# Schematic_v6.net
KiCad netlist of a schematic drawn in EAGLE
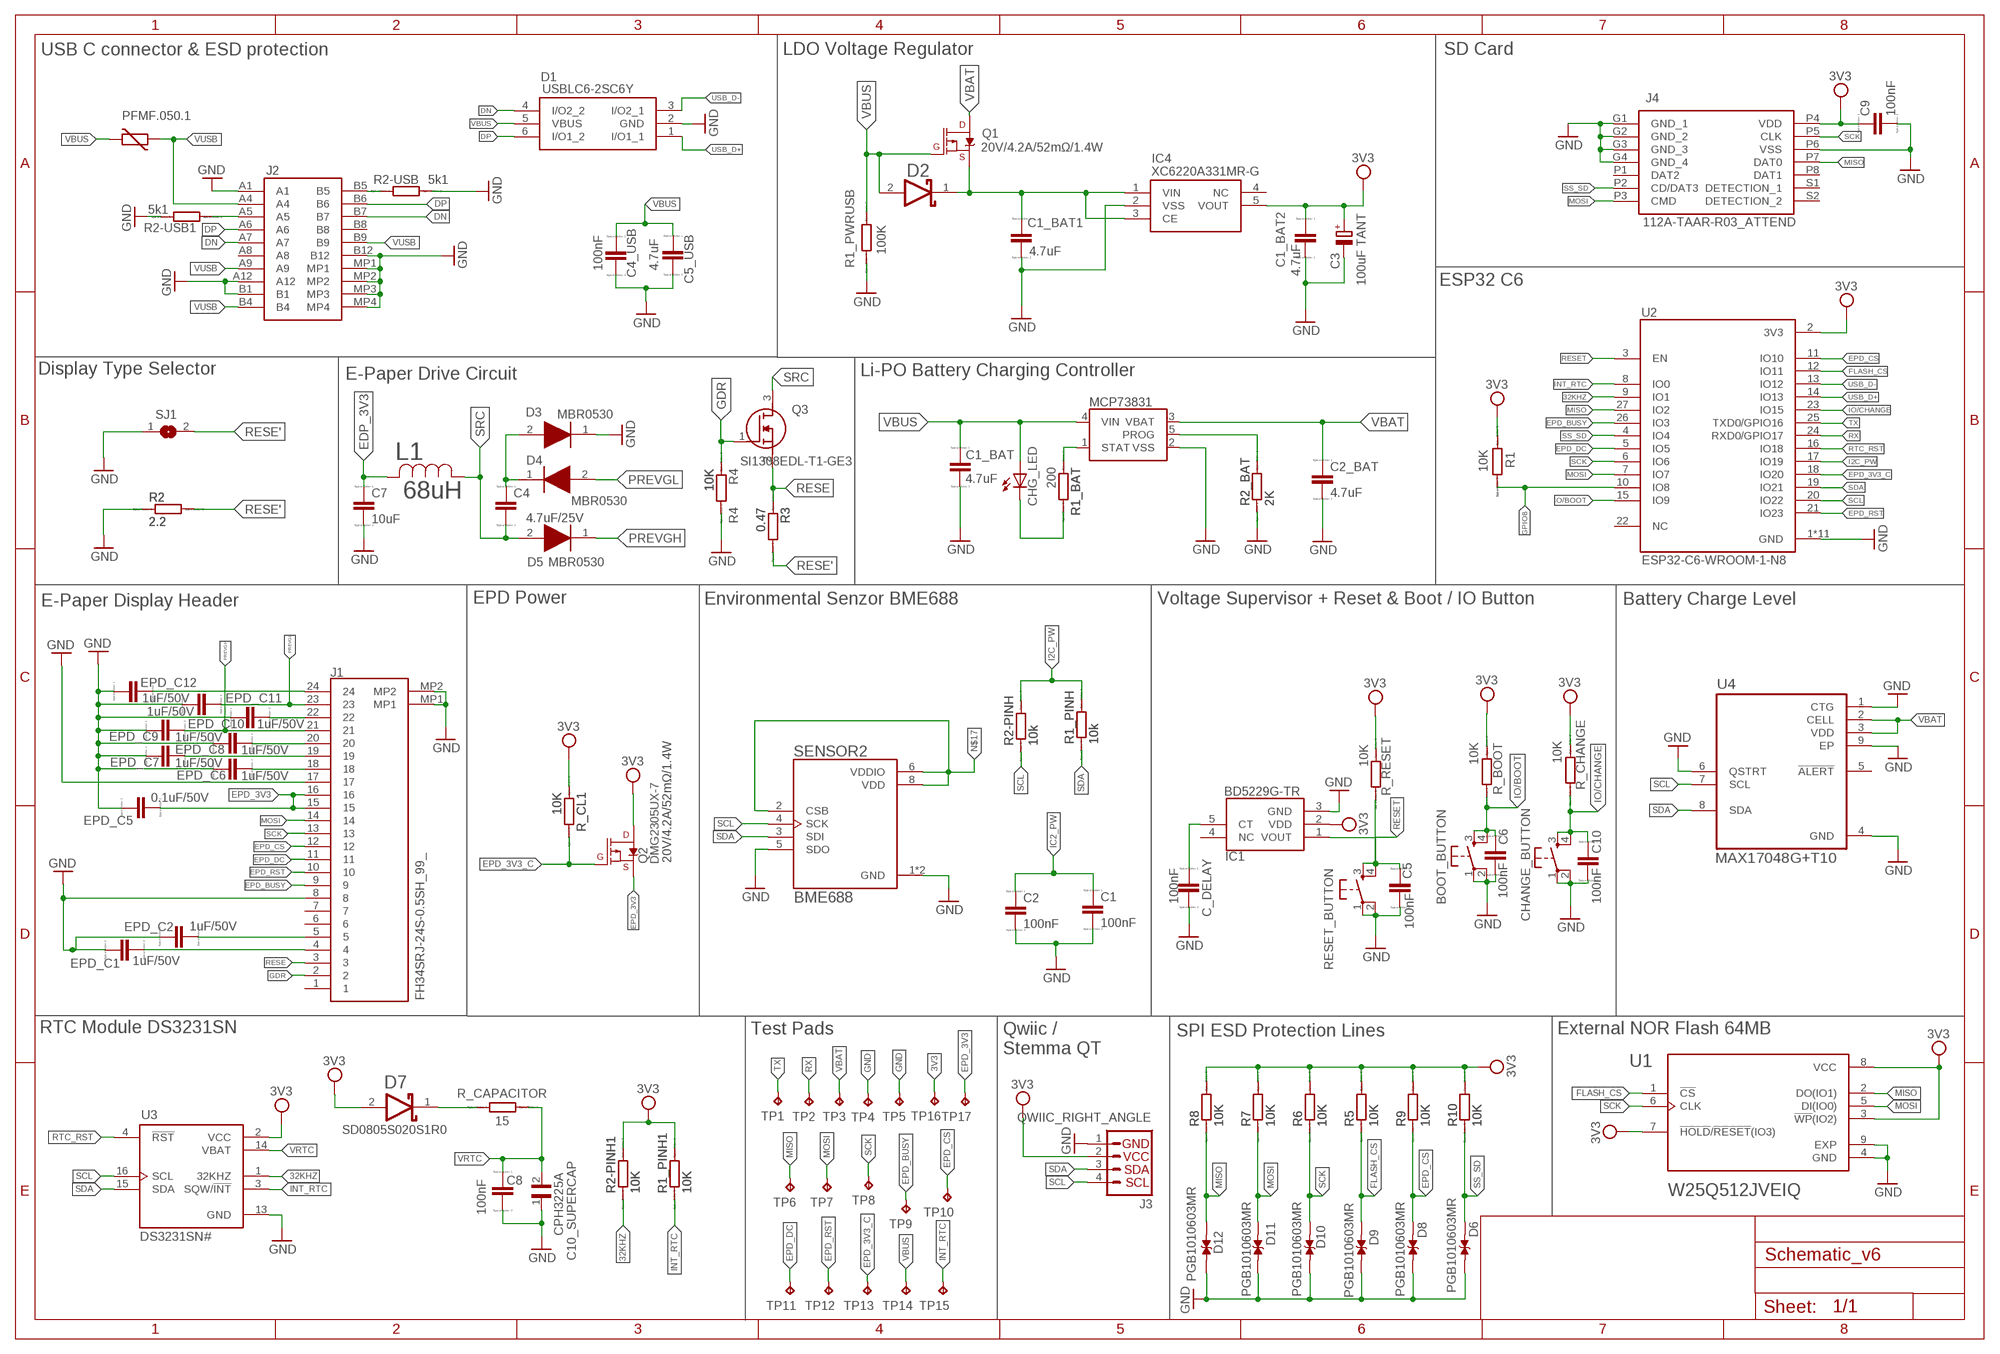
[diagram p0: schematic, sheet 1]

(export (version "E")
  (design (tool "Eeschema 10.0.6"))
  (components
    (comp (ref "BOOT_BUTTON")
      (value "BUTTON_CUSYOMV1")
      (footprint "eagle-import:MYBUTTON")
      (libsource (lib "eagle-import") (part "BUTTON_CUSYOMV1"))
    )
    (comp (ref "C1")
      (value "100nF")
      (footprint "eagle-import:ESP32_WROVER_EAGLE-LTSPICE_C0402")
      (libsource (lib "eagle-import") (part "ESP32_WROVER_EAGLE-LTSPICE_CC0402"))
    )
    (comp (ref "C1_BAT")
      (value "4.7uF")
      (footprint "eagle-import:ESP32_WROVER_EAGLE-LTSPICE_C0402")
      (libsource (lib "eagle-import") (part "ESP32_WROVER_EAGLE-LTSPICE_CC0402"))
    )
    (comp (ref "C1_BAT1")
      (value "4.7uF")
      (footprint "eagle-import:ESP32_WROVER_EAGLE-LTSPICE_C0402")
      (libsource (lib "eagle-import") (part "ESP32_WROVER_EAGLE-LTSPICE_CC0402"))
    )
    (comp (ref "C1_BAT2")
      (value "4.7uF")
      (footprint "eagle-import:ESP32_WROVER_EAGLE-LTSPICE_C0402")
      (libsource (lib "eagle-import") (part "ESP32_WROVER_EAGLE-LTSPICE_CC0402"))
    )
    (comp (ref "C2")
      (value "100nF")
      (footprint "eagle-import:ESP32_WROVER_EAGLE-LTSPICE_C0402")
      (libsource (lib "eagle-import") (part "ESP32_WROVER_EAGLE-LTSPICE_CC0402"))
    )
    (comp (ref "C2_BAT")
      (value "4.7uF")
      (footprint "eagle-import:ESP32_WROVER_EAGLE-LTSPICE_C0402")
      (libsource (lib "eagle-import") (part "ESP32_WROVER_EAGLE-LTSPICE_CC0402"))
    )
    (comp (ref "C3")
      (value "100uF TANT")
      (footprint "eagle-import:RCL_CT3528")
      (libsource (lib "eagle-import") (part "RCL_CPOL-EUCT3528"))
    )
    (comp (ref "C4")
      (value "4.7uF/25V")
      (footprint "eagle-import:ESP32_WROVER_EAGLE-LTSPICE_C0402")
      (libsource (lib "eagle-import") (part "ESP32_WROVER_EAGLE-LTSPICE_CC0402"))
    )
    (comp (ref "C4_USB")
      (value "100nF")
      (footprint "eagle-import:ESP32_WROVER_EAGLE-LTSPICE_C0402")
      (libsource (lib "eagle-import") (part "ESP32_WROVER_EAGLE-LTSPICE_CC0402"))
    )
    (comp (ref "C5")
      (value "100nF")
      (footprint "eagle-import:EAGLE-LTSPICE_C0402")
      (libsource (lib "eagle-import") (part "EAGLE-LTSPICE_CC0402"))
    )
    (comp (ref "C5_USB")
      (value "4.7uF")
      (footprint "eagle-import:ESP32_WROVER_EAGLE-LTSPICE_C0402")
      (libsource (lib "eagle-import") (part "ESP32_WROVER_EAGLE-LTSPICE_CC0402"))
    )
    (comp (ref "C6")
      (value "100nF")
      (footprint "eagle-import:EAGLE-LTSPICE_C0402")
      (libsource (lib "eagle-import") (part "EAGLE-LTSPICE_CC0402"))
    )
    (comp (ref "C7")
      (value "10uF")
      (footprint "eagle-import:ESP32_WROVER_EAGLE-LTSPICE_C0402")
      (libsource (lib "eagle-import") (part "ESP32_WROVER_EAGLE-LTSPICE_CC0402"))
    )
    (comp (ref "C8")
      (value "100nF")
      (footprint "eagle-import:ESP32_WROVER_EAGLE-LTSPICE_C0402")
      (libsource (lib "eagle-import") (part "ESP32_WROVER_EAGLE-LTSPICE_CC0402"))
    )
    (comp (ref "C9")
      (value "100nF")
      (footprint "eagle-import:ESP32_WROVER_EAGLE-LTSPICE_C0402")
      (libsource (lib "eagle-import") (part "ESP32_WROVER_EAGLE-LTSPICE_CC0402"))
    )
    (comp (ref "C10")
      (value "100nF")
      (footprint "eagle-import:EAGLE-LTSPICE_C0402")
      (libsource (lib "eagle-import") (part "EAGLE-LTSPICE_CC0402"))
    )
    (comp (ref "C10_SUPERCAP")
      (value "CPH3225A")
      (footprint "eagle-import:CAPCP3225X100N")
      (fields (field (name "MF") "Seiko Instruments"))
      (libsource (lib "eagle-import") (part "CPH3225A"))
    )
    (comp (ref "CHANGE_BUTTON")
      (value "BUTTON_CUSYOMV1")
      (footprint "eagle-import:MYBUTTON")
      (libsource (lib "eagle-import") (part "BUTTON_CUSYOMV1"))
    )
    (comp (ref "CHG_LED")
      (value "CHG")
      (footprint "eagle-import:ADAFRUIT_CHIP-LED0603")
      (libsource (lib "eagle-import") (part "ADAFRUIT_LEDCHIP-LED0603"))
    )
    (comp (ref "C_DELAY")
      (value "100nF")
      (footprint "eagle-import:ESP32_WROVER_EAGLE-LTSPICE_C0402")
      (libsource (lib "eagle-import") (part "ESP32_WROVER_EAGLE-LTSPICE_CC0402"))
    )
    (comp (ref "D1")
      (value "USBLC6-2SC6Y")
      (footprint "eagle-import:SOT95P280X145-6N")
      (fields (field (name "MF") "STMicroelectronics"))
      (libsource (lib "eagle-import") (part "USBLC6-2SC6Y"))
    )
    (comp (ref "D2")
      (value "ESP32_WROVER_AVX---SD0805S020S1R0_AVX_SD0805S020S1R0_0_0AVX_SD0805S020S1R0_0_0")
      (footprint "eagle-import:ESP32_WROVER_AVX---SD0805S020S1R0_AVX_SD0805S020S1R0_0")
      (fields
        (field (name "DIGIKEY_PART_NUMBER") "478-7800-1-ND")
        (field (name "MF") "AVX")
        (field (name "MOUSER_PART_NUMBER") "581-SD0805S020S1R0")
      )
      (libsource (lib "eagle-import") (part "ESP32_WROVER_AVX---SD0805S020S1R0_AVX_SD0805S020S1R0_0_0AVX_SD0805S020S1R0_0_0"))
    )
    (comp (ref "D3")
      (value "MBR0530")
      (footprint "eagle-import:SOD3716X135N")
      (fields (field (name "MF") "ON Semiconductor"))
      (libsource (lib "eagle-import") (part "MBR0530"))
    )
    (comp (ref "D4")
      (value "MBR0530")
      (footprint "eagle-import:SOD3716X135N")
      (fields (field (name "MF") "ON Semiconductor"))
      (libsource (lib "eagle-import") (part "MBR0530"))
    )
    (comp (ref "D5")
      (value "MBR0530")
      (footprint "eagle-import:SOD3716X135N")
      (fields (field (name "MF") "ON Semiconductor"))
      (libsource (lib "eagle-import") (part "MBR0530"))
    )
    (comp (ref "D6")
      (value "PGB1010603MR")
      (footprint "eagle-import:DIOC1608X36N")
      (fields (field (name "MF") "Littelfuse Inc."))
      (libsource (lib "eagle-import") (part "PGB1010603MR"))
    )
    (comp (ref "D7")
      (value "ESP32_WROVER_AVX---SD0805S020S1R0_AVX_SD0805S020S1R0_0_0AVX_SD0805S020S1R0_0_0")
      (footprint "eagle-import:ESP32_WROVER_AVX---SD0805S020S1R0_AVX_SD0805S020S1R0_0")
      (fields
        (field (name "DIGIKEY_PART_NUMBER") "478-7800-1-ND")
        (field (name "MF") "AVX")
        (field (name "MOUSER_PART_NUMBER") "581-SD0805S020S1R0")
      )
      (libsource (lib "eagle-import") (part "ESP32_WROVER_AVX---SD0805S020S1R0_AVX_SD0805S020S1R0_0_0AVX_SD0805S020S1R0_0_0"))
    )
    (comp (ref "D8")
      (value "PGB1010603MR")
      (footprint "eagle-import:DIOC1608X36N")
      (fields (field (name "MF") "Littelfuse Inc."))
      (libsource (lib "eagle-import") (part "PGB1010603MR"))
    )
    (comp (ref "D9")
      (value "PGB1010603MR")
      (footprint "eagle-import:DIOC1608X36N")
      (fields (field (name "MF") "Littelfuse Inc."))
      (libsource (lib "eagle-import") (part "PGB1010603MR"))
    )
    (comp (ref "D10")
      (value "PGB1010603MR")
      (footprint "eagle-import:DIOC1608X36N")
      (fields (field (name "MF") "Littelfuse Inc."))
      (libsource (lib "eagle-import") (part "PGB1010603MR"))
    )
    (comp (ref "D11")
      (value "PGB1010603MR")
      (footprint "eagle-import:DIOC1608X36N")
      (fields (field (name "MF") "Littelfuse Inc."))
      (libsource (lib "eagle-import") (part "PGB1010603MR"))
    )
    (comp (ref "D12")
      (value "PGB1010603MR")
      (footprint "eagle-import:DIOC1608X36N")
      (fields (field (name "MF") "Littelfuse Inc."))
      (libsource (lib "eagle-import") (part "PGB1010603MR"))
    )
    (comp (ref "EPD_C1")
      (value "1uF/50V")
      (footprint "eagle-import:EAGLE-LTSPICE_C0402")
      (libsource (lib "eagle-import") (part "EAGLE-LTSPICE_CC0402"))
    )
    (comp (ref "EPD_C2")
      (value "1uF/50V")
      (footprint "eagle-import:EAGLE-LTSPICE_C0402")
      (libsource (lib "eagle-import") (part "EAGLE-LTSPICE_CC0402"))
    )
    (comp (ref "EPD_C5")
      (value "0.1uF/50V")
      (footprint "eagle-import:EAGLE-LTSPICE_C0402")
      (libsource (lib "eagle-import") (part "EAGLE-LTSPICE_CC0402"))
    )
    (comp (ref "EPD_C6")
      (value "1uF/50V")
      (footprint "eagle-import:EAGLE-LTSPICE_C0402")
      (libsource (lib "eagle-import") (part "EAGLE-LTSPICE_CC0402"))
    )
    (comp (ref "EPD_C7")
      (value "1uF/50V")
      (footprint "eagle-import:EAGLE-LTSPICE_C0402")
      (libsource (lib "eagle-import") (part "EAGLE-LTSPICE_CC0402"))
    )
    (comp (ref "EPD_C8")
      (value "1uF/50V")
      (footprint "eagle-import:EAGLE-LTSPICE_C0402")
      (libsource (lib "eagle-import") (part "EAGLE-LTSPICE_CC0402"))
    )
    (comp (ref "EPD_C9")
      (value "1uF/50V")
      (footprint "eagle-import:EAGLE-LTSPICE_C0402")
      (libsource (lib "eagle-import") (part "EAGLE-LTSPICE_CC0402"))
    )
    (comp (ref "EPD_C10")
      (value "1uF/50V")
      (footprint "eagle-import:EAGLE-LTSPICE_C0402")
      (libsource (lib "eagle-import") (part "EAGLE-LTSPICE_CC0402"))
    )
    (comp (ref "EPD_C11")
      (value "1uF/50V")
      (footprint "eagle-import:EAGLE-LTSPICE_C0402")
      (libsource (lib "eagle-import") (part "EAGLE-LTSPICE_CC0402"))
    )
    (comp (ref "EPD_C12")
      (value "1uF/50V")
      (footprint "eagle-import:EAGLE-LTSPICE_C0402")
      (libsource (lib "eagle-import") (part "EAGLE-LTSPICE_CC0402"))
    )
    (comp (ref "IC1")
      (value "BD5229G-TR")
      (footprint "eagle-import:SOT95P280X125-5N")
      (fields (field (name "MOUSER_PART_NUMBER") "755-BD5229G-TR"))
      (libsource (lib "eagle-import") (part "BD5229G-TR"))
    )
    (comp (ref "IC4")
      (value "XC6220A331MR-G")
      (footprint "eagle-import:SOT95P280X120-5N")
      (fields (field (name "MOUSER_PART_NUMBER") "865-XC6220A331MR-G"))
      (libsource (lib "eagle-import") (part "XC6220A331MR-G"))
    )
    (comp (ref "J1")
      (value "FH34SRJ-24S-0.5SH_99_")
      (footprint "eagle-import:FH34SRJ24S05SH99")
      (fields
        (field (name "MANUFACTURER_PART_NUMBER") "FH34SRJ-24S-0.5SH(99)")
        (field (name "MOUSER_PART_NUMBER") "798-FH34SRJ24S05SH99")
      )
      (libsource (lib "eagle-import") (part "FH34SRJ-24S-0.5SH_99_"))
    )
    (comp (ref "J2")
      (value "SAMACSYS_PARTS_USB4110-GF-A")
      (footprint "eagle-import:SAMACSYS_PARTS_USB4110GFA")
      (fields
        (field (name "MANUFACTURER_PART_NUMBER") "USB4110-GF-A")
        (field (name "MOUSER_PART_NUMBER") "640-USB4110-GF-A")
      )
      (libsource (lib "eagle-import") (part "SAMACSYS_PARTS_USB4110-GF-A"))
    )
    (comp (ref "J3")
      (value "QWIIC_RIGHT_ANGLE")
      (footprint "eagle-import:JST04_1MM_RA")
      (libsource (lib "eagle-import") (part "QWIIC_CONNECTORJS-1MM"))
    )
    (comp (ref "J4")
      (value "112A-TAAR-R03_ATTEND")
      (footprint "eagle-import:112ATAARR03ATTEND")
      (fields (field (name "MANUFACTURER_PART_NUMBER") "112A-TAAR-R03 ATTEND"))
      (libsource (lib "eagle-import") (part "112A-TAAR-R03_ATTEND"))
    )
    (comp (ref "L1")
      (value "68uH")
      (footprint "eagle-import:IND_4828-WE-TPC_WRE")
      (fields
        (field (name "MANUFACTURER_PART_NUMBER") "744043680")
        (field (name "COPYRIGHT") "Copyright (C) 2024 Ultra Librarian. All rights reserved.")
      )
      (libsource (lib "eagle-import") (part "744043680IND_4828-WE-TPC_WRE"))
    )
    (comp (ref "MCP73831")
      (value "ESP32_WROVER_SPARKFUN-IC-POWER_MCP73831")
      (footprint "eagle-import:ESP32_WROVER_SPARKFUN-IC-POWER_SOT23-5")
      (libsource (lib "eagle-import") (part "ESP32_WROVER_SPARKFUN-IC-POWER_MCP73831"))
    )
    (comp (ref "PFMF.050.1")
      (value "ESP32C6_VARISTORCN1812")
      (footprint "eagle-import:ESP32C6_VARISTOR_CT_CN1812")
      (libsource (lib "eagle-import") (part "ESP32C6_VARISTORCN1812"))
    )
    (comp (ref "Q1")
      (value "20V/4.2A/52mΩ/1.4W")
      (footprint "eagle-import:ESP32_WROVER_SPARKFUN-DISCRETESEMI_SOT23-3")
      (libsource (lib "eagle-import") (part "ESP32_WROVER_SPARKFUN-DISCRETESEMI_MOSFET_PCH-DMG2305UX-7"))
    )
    (comp (ref "Q2")
      (value "20V/4.2A/52mΩ/1.4W")
      (footprint "eagle-import:ESP32_WROVER_SPARKFUN-DISCRETESEMI_SOT23-3")
      (libsource (lib "eagle-import") (part "ESP32_WROVER_SPARKFUN-DISCRETESEMI_MOSFET_PCH-DMG2305UX-7"))
    )
    (comp (ref "Q3")
      (value "SI1308EDL-T1-GE3")
      (footprint "eagle-import:SOT65P210X110-3N")
      (fields (field (name "MF") "Vishay Siliconix"))
      (libsource (lib "eagle-import") (part "SI1308EDL-T1-GE3"))
    )
    (comp (ref "R1")
      (value "10K")
      (footprint "eagle-import:ESP32_WROVER_EAGLE-LTSPICE_R0402")
      (libsource (lib "eagle-import") (part "ESP32_WROVER_EAGLE-LTSPICE_RR0402"))
    )
    (comp (ref "R1_BAT")
      (value "200")
      (footprint "eagle-import:ESP32_WROVER_EAGLE-LTSPICE_R0402")
      (libsource (lib "eagle-import") (part "ESP32_WROVER_EAGLE-LTSPICE_RR0402"))
    )
    (comp (ref "R1_PINH")
      (value "10k")
      (footprint "eagle-import:ESP32_WROVER_EAGLE-LTSPICE_R0402")
      (libsource (lib "eagle-import") (part "ESP32_WROVER_EAGLE-LTSPICE_RR0402"))
    )
    (comp (ref "R1_PINH1")
      (value "10K")
      (footprint "eagle-import:ESP32_WROVER_EAGLE-LTSPICE_R0402")
      (libsource (lib "eagle-import") (part "ESP32_WROVER_EAGLE-LTSPICE_RR0402"))
    )
    (comp (ref "R1_PWRUSB")
      (value "100K")
      (footprint "eagle-import:ESP32_WROVER_EAGLE-LTSPICE_R0402")
      (libsource (lib "eagle-import") (part "ESP32_WROVER_EAGLE-LTSPICE_RR0402"))
    )
    (comp (ref "R2")
      (value "2.2")
      (footprint "eagle-import:ESP32_WROVER_EAGLE-LTSPICE_R0402")
      (libsource (lib "eagle-import") (part "ESP32_WROVER_EAGLE-LTSPICE_RR0402"))
    )
    (comp (ref "R2-PINH")
      (value "10k")
      (footprint "eagle-import:ESP32_WROVER_EAGLE-LTSPICE_R0402")
      (libsource (lib "eagle-import") (part "ESP32_WROVER_EAGLE-LTSPICE_RR0402"))
    )
    (comp (ref "R2-PINH1")
      (value "10K")
      (footprint "eagle-import:ESP32_WROVER_EAGLE-LTSPICE_R0402")
      (libsource (lib "eagle-import") (part "ESP32_WROVER_EAGLE-LTSPICE_RR0402"))
    )
    (comp (ref "R2-USB")
      (value "5k1")
      (footprint "eagle-import:ESP32_WROVER_EAGLE-LTSPICE_R0402")
      (libsource (lib "eagle-import") (part "ESP32_WROVER_EAGLE-LTSPICE_RR0402"))
    )
    (comp (ref "R2-USB1")
      (value "5k1")
      (footprint "eagle-import:ESP32_WROVER_EAGLE-LTSPICE_R0402")
      (libsource (lib "eagle-import") (part "ESP32_WROVER_EAGLE-LTSPICE_RR0402"))
    )
    (comp (ref "R2_BAT")
      (value "2K")
      (footprint "eagle-import:ESP32_WROVER_EAGLE-LTSPICE_R0402")
      (libsource (lib "eagle-import") (part "ESP32_WROVER_EAGLE-LTSPICE_RR0402"))
    )
    (comp (ref "R3")
      (value "0.47")
      (footprint "eagle-import:ESP32_WROVER_EAGLE-LTSPICE_R0402")
      (libsource (lib "eagle-import") (part "ESP32_WROVER_EAGLE-LTSPICE_RR0402"))
    )
    (comp (ref "R4")
      (value "10K")
      (footprint "eagle-import:ESP32_WROVER_EAGLE-LTSPICE_R0402")
      (libsource (lib "eagle-import") (part "ESP32_WROVER_EAGLE-LTSPICE_RR0402"))
    )
    (comp (ref "R5")
      (value "10K")
      (footprint "eagle-import:ESP32_WROVER_EAGLE-LTSPICE_R0402")
      (libsource (lib "eagle-import") (part "ESP32_WROVER_EAGLE-LTSPICE_RR0402"))
    )
    (comp (ref "R6")
      (value "10K")
      (footprint "eagle-import:ESP32_WROVER_EAGLE-LTSPICE_R0402")
      (libsource (lib "eagle-import") (part "ESP32_WROVER_EAGLE-LTSPICE_RR0402"))
    )
    (comp (ref "R7")
      (value "10K")
      (footprint "eagle-import:ESP32_WROVER_EAGLE-LTSPICE_R0402")
      (libsource (lib "eagle-import") (part "ESP32_WROVER_EAGLE-LTSPICE_RR0402"))
    )
    (comp (ref "R8")
      (value "10K")
      (footprint "eagle-import:ESP32_WROVER_EAGLE-LTSPICE_R0402")
      (libsource (lib "eagle-import") (part "ESP32_WROVER_EAGLE-LTSPICE_RR0402"))
    )
    (comp (ref "R9")
      (value "10K")
      (footprint "eagle-import:ESP32_WROVER_EAGLE-LTSPICE_R0402")
      (libsource (lib "eagle-import") (part "ESP32_WROVER_EAGLE-LTSPICE_RR0402"))
    )
    (comp (ref "R10")
      (value "10K")
      (footprint "eagle-import:ESP32_WROVER_EAGLE-LTSPICE_R0402")
      (libsource (lib "eagle-import") (part "ESP32_WROVER_EAGLE-LTSPICE_RR0402"))
    )
    (comp (ref "RESET_BUTTON")
      (value "BUTTON_CUSYOMV1")
      (footprint "eagle-import:MYBUTTON")
      (libsource (lib "eagle-import") (part "BUTTON_CUSYOMV1"))
    )
    (comp (ref "R_BOOT")
      (value "10K")
      (footprint "eagle-import:ESP32_WROVER_EAGLE-LTSPICE_R0402")
      (libsource (lib "eagle-import") (part "ESP32_WROVER_EAGLE-LTSPICE_RR0402"))
    )
    (comp (ref "R_CAPACITOR")
      (value "15")
      (footprint "eagle-import:ESP32_WROVER_EAGLE-LTSPICE_R0402")
      (libsource (lib "eagle-import") (part "ESP32_WROVER_EAGLE-LTSPICE_RR0402"))
    )
    (comp (ref "R_CHANGE")
      (value "10K")
      (footprint "eagle-import:ESP32_WROVER_EAGLE-LTSPICE_R0402")
      (libsource (lib "eagle-import") (part "ESP32_WROVER_EAGLE-LTSPICE_RR0402"))
    )
    (comp (ref "R_CL1")
      (value "10K")
      (footprint "eagle-import:ESP32_WROVER_EAGLE-LTSPICE_R0402")
      (libsource (lib "eagle-import") (part "ESP32_WROVER_EAGLE-LTSPICE_RR0402"))
    )
    (comp (ref "R_RESET")
      (value "10K")
      (footprint "eagle-import:ESP32_WROVER_EAGLE-LTSPICE_R0402")
      (libsource (lib "eagle-import") (part "ESP32_WROVER_EAGLE-LTSPICE_RR0402"))
    )
    (comp (ref "SENSOR2")
      (value "BME688")
      (footprint "eagle-import:ESP32_WROVER_BME680_PSON80P300X300X100-8N")
      (fields (field (name "MF") "Bosch Sensortec") (field (name "MP") "BME680"))
      (libsource (lib "eagle-import") (part "ESP32_WROVER_BME680_BME680"))
    )
    (comp (ref "SJ1")
      (value "SJ1")
      (footprint "eagle-import:SJ")
      (libsource (lib "eagle-import") (part "SJ"))
    )
    (comp (ref "TP1")
      (value "TPTP20R")
      (footprint "eagle-import:TP20R")
      (libsource (lib "eagle-import") (part "TPTP20R"))
    )
    (comp (ref "TP2")
      (value "TPTP20R")
      (footprint "eagle-import:TP20R")
      (libsource (lib "eagle-import") (part "TPTP20R"))
    )
    (comp (ref "TP3")
      (value "TPTP20R")
      (footprint "eagle-import:TP20R")
      (libsource (lib "eagle-import") (part "TPTP20R"))
    )
    (comp (ref "TP4")
      (value "TPTP20R")
      (footprint "eagle-import:TP20R")
      (libsource (lib "eagle-import") (part "TPTP20R"))
    )
    (comp (ref "TP5")
      (value "TPTP20R")
      (footprint "eagle-import:TP20R")
      (libsource (lib "eagle-import") (part "TPTP20R"))
    )
    (comp (ref "TP6")
      (value "TPTP20R")
      (footprint "eagle-import:TP20R")
      (libsource (lib "eagle-import") (part "TPTP20R"))
    )
    (comp (ref "TP7")
      (value "TPTP20R")
      (footprint "eagle-import:TP20R")
      (libsource (lib "eagle-import") (part "TPTP20R"))
    )
    (comp (ref "TP8")
      (value "TPTP20R")
      (footprint "eagle-import:TP20R")
      (libsource (lib "eagle-import") (part "TPTP20R"))
    )
    (comp (ref "TP9")
      (value "TPTP20R")
      (footprint "eagle-import:TP20R")
      (libsource (lib "eagle-import") (part "TPTP20R"))
    )
    (comp (ref "TP10")
      (value "TPTP20R")
      (footprint "eagle-import:TP20R")
      (libsource (lib "eagle-import") (part "TPTP20R"))
    )
    (comp (ref "TP11")
      (value "TPTP20R")
      (footprint "eagle-import:TP20R")
      (libsource (lib "eagle-import") (part "TPTP20R"))
    )
    (comp (ref "TP12")
      (value "TPTP20R")
      (footprint "eagle-import:TP20R")
      (libsource (lib "eagle-import") (part "TPTP20R"))
    )
    (comp (ref "TP13")
      (value "TPTP20R")
      (footprint "eagle-import:TP20R")
      (libsource (lib "eagle-import") (part "TPTP20R"))
    )
    (comp (ref "TP14")
      (value "TPTP20R")
      (footprint "eagle-import:TP20R")
      (libsource (lib "eagle-import") (part "TPTP20R"))
    )
    (comp (ref "TP15")
      (value "TPTP20R")
      (footprint "eagle-import:TP20R")
      (libsource (lib "eagle-import") (part "TPTP20R"))
    )
    (comp (ref "TP16")
      (value "TPTP20R")
      (footprint "eagle-import:TP20R")
      (libsource (lib "eagle-import") (part "TPTP20R"))
    )
    (comp (ref "TP17")
      (value "TPTP20R")
      (footprint "eagle-import:TP20R")
      (libsource (lib "eagle-import") (part "TPTP20R"))
    )
    (comp (ref "U1")
      (value "W25Q512JVEIQ")
      (footprint "eagle-import:SON127P600X800X80-9N")
      (fields (field (name "MF") "Winbond Electronics"))
      (libsource (lib "eagle-import") (part "W25Q512JVEIQ"))
    )
    (comp (ref "U2")
      (value "ESP32-C6-WROOM-1-N8")
      (footprint "eagle-import:XCVR_ESP32-C6-WROOM-1-N8")
      (fields (field (name "MF") "Espressif Systems"))
      (libsource (lib "eagle-import") (part "ESP32-C6-WROOM-1-N8"))
    )
    (comp (ref "U3")
      (value "DS3231SN#")
      (footprint "eagle-import:SOIC127P1032X265-16N")
      (fields (field (name "MF") "Analog Devices"))
      (libsource (lib "eagle-import") (part "DS3231SN#"))
    )
    (comp (ref "U4")
      (value "MAX17048G+T10")
      (footprint "eagle-import:SON50P200X200X80-9N")
      (fields (field (name "MF") "Analog Devices"))
      (libsource (lib "eagle-import") (part "MAX17048G+T10"))
    )
  )
  (nets
    (net (code "1") (name "3V3") (class "Default")
      (node (ref "C1_BAT2") (pin "1") (pinfunction "1_1") (pintype "passive"))
      (node (ref "C3") (pin "+") (pinfunction "+_+") (pintype "passive"))
      (node (ref "C9") (pin "1") (pinfunction "1_1") (pintype "passive"))
      (node (ref "D7") (pin "2") (pinfunction "ANODE_2") (pintype "bidirectional"))
      (node (ref "IC4") (pin "5") (pinfunction "VOUT_5") (pintype "bidirectional"))
      (node (ref "J3") (pin "2") (pinfunction "2_2") (pintype "power_in"))
      (node (ref "J4") (pin "P4") (pinfunction "VDD_P4") (pintype "bidirectional"))
      (node (ref "Q2") (pin "3") (pinfunction "D_3") (pintype "bidirectional"))
      (node (ref "R1") (pin "1") (pinfunction "1_1") (pintype "passive"))
      (node (ref "R10") (pin "2") (pinfunction "2_2") (pintype "passive"))
      (node (ref "R1_PINH1") (pin "2") (pinfunction "2_2") (pintype "passive"))
      (node (ref "R2-PINH1") (pin "2") (pinfunction "2_2") (pintype "passive"))
      (node (ref "R5") (pin "2") (pinfunction "2_2") (pintype "passive"))
      (node (ref "R6") (pin "2") (pinfunction "2_2") (pintype "passive"))
      (node (ref "R7") (pin "2") (pinfunction "2_2") (pintype "passive"))
      (node (ref "R8") (pin "2") (pinfunction "2_2") (pintype "passive"))
      (node (ref "R9") (pin "2") (pinfunction "2_2") (pintype "passive"))
      (node (ref "R_BOOT") (pin "2") (pinfunction "2_2") (pintype "passive"))
      (node (ref "R_CHANGE") (pin "2") (pinfunction "2_2") (pintype "passive"))
      (node (ref "R_CL1") (pin "1") (pinfunction "1_1") (pintype "passive"))
      (node (ref "R_RESET") (pin "2") (pinfunction "2_2") (pintype "passive"))
      (node (ref "TP16") (pin "TP") (pinfunction "TP_TP") (pintype "input"))
      (node (ref "U1") (pin "3") (pinfunction "~{WP}(IO2)_3") (pintype "bidirectional"))
      (node (ref "U1") (pin "7") (pinfunction "~{HOLD}/~{RESET}(IO3)_7") (pintype "bidirectional"))
      (node (ref "U1") (pin "8") (pinfunction "VCC_8") (pintype "power_in"))
      (node (ref "U2") (pin "2") (pinfunction "3V3_2") (pintype "power_in"))
      (node (ref "U3") (pin "2") (pinfunction "VCC_2") (pintype "power_in"))
    )
    (net (code "2") (name "32KHZ") (class "Default")
      (node (ref "R2-PINH1") (pin "1") (pinfunction "1_1") (pintype "passive"))
      (node (ref "U2") (pin "9") (pinfunction "IO1_9") (pintype "bidirectional"))
      (node (ref "U3") (pin "1") (pinfunction "32KHZ_1") (pintype "output"))
    )
    (net (code "3") (name "DN") (class "Default")
      (node (ref "D1") (pin "4") (pinfunction "I/O2_2_4") (pintype "bidirectional"))
      (node (ref "J2") (pin "A7") (pinfunction "A7_A7") (pintype "bidirectional"))
      (node (ref "J2") (pin "B7") (pinfunction "B7_B7") (pintype "bidirectional"))
    )
    (net (code "4") (name "DP") (class "Default")
      (node (ref "D1") (pin "6") (pinfunction "I/O1_2_6") (pintype "bidirectional"))
      (node (ref "J2") (pin "A6") (pinfunction "A6_A6") (pintype "bidirectional"))
      (node (ref "J2") (pin "B6") (pinfunction "B6_B6") (pintype "bidirectional"))
    )
    (net (code "5") (name "EDP_3V3") (class "Default")
      (node (ref "C7") (pin "1") (pinfunction "1_1") (pintype "passive"))
      (node (ref "L1") (pin "2") (pinfunction "2_2") (pintype "passive"))
    )
    (net (code "6") (name "EPD_3V3") (class "Default")
      (node (ref "EPD_C5") (pin "2") (pinfunction "2_2") (pintype "passive"))
      (node (ref "J1") (pin "15") (pinfunction "15_15") (pintype "bidirectional"))
      (node (ref "J1") (pin "16") (pinfunction "16_16") (pintype "bidirectional"))
      (node (ref "Q2") (pin "2") (pinfunction "S_2") (pintype "bidirectional"))
      (node (ref "TP17") (pin "TP") (pinfunction "TP_TP") (pintype "input"))
    )
    (net (code "7") (name "EPD_3V3_C") (class "Default")
      (node (ref "Q2") (pin "1") (pinfunction "G_1") (pintype "bidirectional"))
      (node (ref "R_CL1") (pin "2") (pinfunction "2_2") (pintype "passive"))
      (node (ref "TP13") (pin "TP") (pinfunction "TP_TP") (pintype "input"))
      (node (ref "U2") (pin "18") (pinfunction "IO20_18") (pintype "bidirectional"))
    )
    (net (code "8") (name "EPD_BUSY") (class "Default")
      (node (ref "J1") (pin "9") (pinfunction "9_9") (pintype "bidirectional"))
      (node (ref "TP9") (pin "TP") (pinfunction "TP_TP") (pintype "input"))
      (node (ref "U2") (pin "26") (pinfunction "IO3_26") (pintype "bidirectional"))
    )
    (net (code "9") (name "EPD_CS") (class "Default")
      (node (ref "D8") (pin "1") (pinfunction "1_1") (pintype "passive"))
      (node (ref "J1") (pin "12") (pinfunction "12_12") (pintype "bidirectional"))
      (node (ref "R9") (pin "1") (pinfunction "1_1") (pintype "passive"))
      (node (ref "TP10") (pin "TP") (pinfunction "TP_TP") (pintype "input"))
      (node (ref "U2") (pin "11") (pinfunction "IO10_11") (pintype "bidirectional"))
    )
    (net (code "10") (name "EPD_DC") (class "Default")
      (node (ref "J1") (pin "11") (pinfunction "11_11") (pintype "bidirectional"))
      (node (ref "TP11") (pin "TP") (pinfunction "TP_TP") (pintype "input"))
      (node (ref "U2") (pin "5") (pinfunction "IO5_5") (pintype "bidirectional"))
    )
    (net (code "11") (name "EPD_RST") (class "Default")
      (node (ref "J1") (pin "10") (pinfunction "10_10") (pintype "bidirectional"))
      (node (ref "TP12") (pin "TP") (pinfunction "TP_TP") (pintype "input"))
      (node (ref "U2") (pin "21") (pinfunction "IO23_21") (pintype "bidirectional"))
    )
    (net (code "12") (name "FLASH_CS") (class "Default")
      (node (ref "D9") (pin "1") (pinfunction "1_1") (pintype "passive"))
      (node (ref "R5") (pin "1") (pinfunction "1_1") (pintype "passive"))
      (node (ref "U1") (pin "1") (pinfunction "~{CS}_1") (pintype "input"))
      (node (ref "U2") (pin "12") (pinfunction "IO11_12") (pintype "bidirectional"))
    )
    (net (code "13") (name "GDR") (class "Default")
      (node (ref "J1") (pin "2") (pinfunction "2_2") (pintype "bidirectional"))
      (node (ref "Q3") (pin "1") (pinfunction "G_1") (pintype "bidirectional"))
      (node (ref "R4") (pin "1") (pinfunction "1_1") (pintype "passive"))
    )
    (net (code "14") (name "GND") (class "Default")
      (node (ref "BOOT_BUTTON") (pin "1") (pinfunction "1_1") (pintype "passive"))
      (node (ref "BOOT_BUTTON") (pin "2") (pinfunction "2_2") (pintype "passive"))
      (node (ref "C1") (pin "2") (pinfunction "2_2") (pintype "passive"))
      (node (ref "C10") (pin "2") (pinfunction "2_2") (pintype "passive"))
      (node (ref "C10_SUPERCAP") (pin "1") (pinfunction "1_1") (pintype "passive"))
      (node (ref "C1_BAT") (pin "2") (pinfunction "2_2") (pintype "passive"))
      (node (ref "C1_BAT1") (pin "2") (pinfunction "2_2") (pintype "passive"))
      (node (ref "C1_BAT2") (pin "2") (pinfunction "2_2") (pintype "passive"))
      (node (ref "C2") (pin "2") (pinfunction "2_2") (pintype "passive"))
      (node (ref "C2_BAT") (pin "2") (pinfunction "2_2") (pintype "passive"))
      (node (ref "C3") (pin "-") (pinfunction "-_-") (pintype "passive"))
      (node (ref "C4_USB") (pin "2") (pinfunction "2_2") (pintype "passive"))
      (node (ref "C5") (pin "2") (pinfunction "2_2") (pintype "passive"))
      (node (ref "C5_USB") (pin "2") (pinfunction "2_2") (pintype "passive"))
      (node (ref "C6") (pin "2") (pinfunction "2_2") (pintype "passive"))
      (node (ref "C7") (pin "2") (pinfunction "2_2") (pintype "passive"))
      (node (ref "C8") (pin "2") (pinfunction "2_2") (pintype "passive"))
      (node (ref "C9") (pin "2") (pinfunction "2_2") (pintype "passive"))
      (node (ref "CHANGE_BUTTON") (pin "1") (pinfunction "1_1") (pintype "passive"))
      (node (ref "CHANGE_BUTTON") (pin "2") (pinfunction "2_2") (pintype "passive"))
      (node (ref "C_DELAY") (pin "2") (pinfunction "2_2") (pintype "passive"))
      (node (ref "D1") (pin "2") (pinfunction "GND_2") (pintype "bidirectional"))
      (node (ref "D10") (pin "2") (pinfunction "2_2") (pintype "passive"))
      (node (ref "D11") (pin "2") (pinfunction "2_2") (pintype "passive"))
      (node (ref "D12") (pin "2") (pinfunction "2_2") (pintype "passive"))
      (node (ref "D3") (pin "1") (pinfunction "K_1") (pintype "bidirectional"))
      (node (ref "D6") (pin "2") (pinfunction "2_2") (pintype "passive"))
      (node (ref "D8") (pin "2") (pinfunction "2_2") (pintype "passive"))
      (node (ref "D9") (pin "2") (pinfunction "2_2") (pintype "passive"))
      (node (ref "EPD_C1") (pin "1") (pinfunction "1_1") (pintype "passive"))
      (node (ref "EPD_C10") (pin "1") (pinfunction "1_1") (pintype "passive"))
      (node (ref "EPD_C11") (pin "1") (pinfunction "1_1") (pintype "passive"))
      (node (ref "EPD_C12") (pin "1") (pinfunction "1_1") (pintype "passive"))
      (node (ref "EPD_C2") (pin "1") (pinfunction "1_1") (pintype "passive"))
      (node (ref "EPD_C5") (pin "1") (pinfunction "1_1") (pintype "passive"))
      (node (ref "EPD_C6") (pin "1") (pinfunction "1_1") (pintype "passive"))
      (node (ref "EPD_C7") (pin "1") (pinfunction "1_1") (pintype "passive"))
      (node (ref "EPD_C8") (pin "1") (pinfunction "1_1") (pintype "passive"))
      (node (ref "EPD_C9") (pin "1") (pinfunction "1_1") (pintype "passive"))
      (node (ref "IC1") (pin "3") (pinfunction "GND_3") (pintype "bidirectional"))
      (node (ref "IC4") (pin "2") (pinfunction "VSS_2") (pintype "bidirectional"))
      (node (ref "J1") (pin "17") (pinfunction "17_17") (pintype "bidirectional"))
      (node (ref "J1") (pin "8") (pinfunction "8_8") (pintype "bidirectional"))
      (node (ref "J1") (pin "MP1") (pinfunction "MP1_MP1") (pintype "bidirectional"))
      (node (ref "J1") (pin "MP2") (pinfunction "MP2_MP2") (pintype "bidirectional"))
      (node (ref "J2") (pin "A1") (pinfunction "A1_A1") (pintype "bidirectional"))
      (node (ref "J2") (pin "A12") (pinfunction "A12_A12") (pintype "bidirectional"))
      (node (ref "J2") (pin "B1") (pinfunction "B1_B1") (pintype "bidirectional"))
      (node (ref "J2") (pin "B12") (pinfunction "B12_B12") (pintype "bidirectional"))
      (node (ref "J2") (pin "MP1") (pinfunction "MP1_MP1") (pintype "bidirectional"))
      (node (ref "J2") (pin "MP2") (pinfunction "MP2_MP2") (pintype "bidirectional"))
      (node (ref "J2") (pin "MP3") (pinfunction "MP3_MP3") (pintype "bidirectional"))
      (node (ref "J2") (pin "MP4") (pinfunction "MP4_MP4") (pintype "bidirectional"))
      (node (ref "J3") (pin "1") (pinfunction "1_1") (pintype "power_in"))
      (node (ref "J4") (pin "G1") (pinfunction "GND_1_G1") (pintype "bidirectional"))
      (node (ref "J4") (pin "G2") (pinfunction "GND_2_G2") (pintype "bidirectional"))
      (node (ref "J4") (pin "G3") (pinfunction "GND_3_G3") (pintype "bidirectional"))
      (node (ref "J4") (pin "G4") (pinfunction "GND_4_G4") (pintype "bidirectional"))
      (node (ref "J4") (pin "P6") (pinfunction "VSS_P6") (pintype "bidirectional"))
      (node (ref "MCP73831") (pin "2") (pinfunction "VSS_2") (pintype "power_in"))
      (node (ref "R1_PWRUSB") (pin "1") (pinfunction "1_1") (pintype "passive"))
      (node (ref "R2") (pin "1") (pinfunction "1_1") (pintype "passive"))
      (node (ref "R2-USB") (pin "2") (pinfunction "2_2") (pintype "passive"))
      (node (ref "R2-USB1") (pin "1") (pinfunction "1_1") (pintype "passive"))
      (node (ref "R2_BAT") (pin "1") (pinfunction "1_1") (pintype "passive"))
      (node (ref "R4") (pin "2") (pinfunction "2_2") (pintype "passive"))
      (node (ref "RESET_BUTTON") (pin "1") (pinfunction "1_1") (pintype "passive"))
      (node (ref "RESET_BUTTON") (pin "2") (pinfunction "2_2") (pintype "passive"))
      (node (ref "SENSOR2") (pin "1") (pinfunction "GND_1") (pintype "power_in"))
      (node (ref "SENSOR2") (pin "5") (pinfunction "SDO_5") (pintype "bidirectional"))
      (node (ref "SENSOR2") (pin "7") (pinfunction "GND_7") (pintype "power_in"))
      (node (ref "SJ1") (pin "1") (pinfunction "1_1") (pintype "passive"))
      (node (ref "TP4") (pin "TP") (pinfunction "TP_TP") (pintype "input"))
      (node (ref "TP5") (pin "TP") (pinfunction "TP_TP") (pintype "input"))
      (node (ref "U1") (pin "4") (pinfunction "GND_4") (pintype "power_in"))
      (node (ref "U1") (pin "9") (pinfunction "EXP_9") (pintype "passive"))
      (node (ref "U2") (pin "1") (pinfunction "GND_1") (pintype "power_in"))
      (node (ref "U2") (pin "28") (pinfunction "GND_28") (pintype "power_in"))
      (node (ref "U2") (pin "29_1") (pinfunction "GND_29_1") (pintype "power_in"))
      (node (ref "U2") (pin "29_2") (pinfunction "GND_29_2") (pintype "power_in"))
      (node (ref "U2") (pin "29_3") (pinfunction "GND_29_3") (pintype "power_in"))
      (node (ref "U2") (pin "29_4") (pinfunction "GND_29_4") (pintype "power_in"))
      (node (ref "U2") (pin "29_5") (pinfunction "GND_29_5") (pintype "power_in"))
      (node (ref "U2") (pin "29_6") (pinfunction "GND_29_6") (pintype "power_in"))
      (node (ref "U2") (pin "29_7") (pinfunction "GND_29_7") (pintype "power_in"))
      (node (ref "U2") (pin "29_8") (pinfunction "GND_29_8") (pintype "power_in"))
      (node (ref "U2") (pin "29_9") (pinfunction "GND_29_9") (pintype "power_in"))
      (node (ref "U3") (pin "13") (pinfunction "GND_13") (pintype "power_in"))
      (node (ref "U4") (pin "1") (pinfunction "CTG_1") (pintype "power_in"))
      (node (ref "U4") (pin "4") (pinfunction "GND_4") (pintype "power_in"))
      (node (ref "U4") (pin "6") (pinfunction "QSTRT_6") (pintype "input"))
      (node (ref "U4") (pin "9") (pinfunction "EP_9") (pintype "power_in"))
    )
    (net (code "15") (name "GPIO8") (class "Default")
      (node (ref "R1") (pin "2") (pinfunction "2_2") (pintype "passive"))
      (node (ref "U2") (pin "10") (pinfunction "IO8_10") (pintype "bidirectional"))
    )
    (net (code "16") (name "I2C_PW") (class "Default")
      (node (ref "R1_PINH") (pin "2") (pinfunction "2_2") (pintype "passive"))
      (node (ref "R2-PINH") (pin "2") (pinfunction "2_2") (pintype "passive"))
      (node (ref "U2") (pin "17") (pinfunction "IO19_17") (pintype "bidirectional"))
    )
    (net (code "17") (name "IC2_PW") (class "Default")
      (node (ref "C1") (pin "1") (pinfunction "1_1") (pintype "passive"))
      (node (ref "C2") (pin "1") (pinfunction "1_1") (pintype "passive"))
    )
    (net (code "18") (name "INT_RTC") (class "Default")
      (node (ref "R1_PINH1") (pin "1") (pinfunction "1_1") (pintype "passive"))
      (node (ref "TP15") (pin "TP") (pinfunction "TP_TP") (pintype "input"))
      (node (ref "U2") (pin "8") (pinfunction "IO0_8") (pintype "bidirectional"))
      (node (ref "U3") (pin "3") (pinfunction "SQW/~{INT}_3") (pintype "output"))
    )
    (net (code "19") (name "IO{slash}BOOT") (class "Default")
      (node (ref "BOOT_BUTTON") (pin "3") (pinfunction "3_3") (pintype "passive"))
      (node (ref "BOOT_BUTTON") (pin "4") (pinfunction "4_4") (pintype "passive"))
      (node (ref "C6") (pin "1") (pinfunction "1_1") (pintype "passive"))
      (node (ref "R_BOOT") (pin "1") (pinfunction "1_1") (pintype "passive"))
      (node (ref "U2") (pin "15") (pinfunction "IO9_15") (pintype "bidirectional"))
    )
    (net (code "20") (name "IO{slash}CHANGE") (class "Default")
      (node (ref "C10") (pin "1") (pinfunction "1_1") (pintype "passive"))
      (node (ref "CHANGE_BUTTON") (pin "3") (pinfunction "3_3") (pintype "passive"))
      (node (ref "CHANGE_BUTTON") (pin "4") (pinfunction "4_4") (pintype "passive"))
      (node (ref "R_CHANGE") (pin "1") (pinfunction "1_1") (pintype "passive"))
      (node (ref "U2") (pin "23") (pinfunction "IO15_23") (pintype "bidirectional"))
    )
    (net (code "21") (name "MISO") (class "Default")
      (node (ref "D12") (pin "1") (pinfunction "1_1") (pintype "passive"))
      (node (ref "J4") (pin "P7") (pinfunction "DAT0_P7") (pintype "bidirectional"))
      (node (ref "R8") (pin "1") (pinfunction "1_1") (pintype "passive"))
      (node (ref "TP6") (pin "TP") (pinfunction "TP_TP") (pintype "input"))
      (node (ref "U1") (pin "2") (pinfunction "DO(IO1)_2") (pintype "bidirectional"))
      (node (ref "U2") (pin "27") (pinfunction "IO2_27") (pintype "bidirectional"))
    )
    (net (code "22") (name "MOSI") (class "Default")
      (node (ref "D11") (pin "1") (pinfunction "1_1") (pintype "passive"))
      (node (ref "J1") (pin "14") (pinfunction "14_14") (pintype "bidirectional"))
      (node (ref "J4") (pin "P3") (pinfunction "CMD_P3") (pintype "bidirectional"))
      (node (ref "R7") (pin "1") (pinfunction "1_1") (pintype "passive"))
      (node (ref "TP7") (pin "TP") (pinfunction "TP_TP") (pintype "input"))
      (node (ref "U1") (pin "5") (pinfunction "DI(IO0)_5") (pintype "bidirectional"))
      (node (ref "U2") (pin "7") (pinfunction "IO7_7") (pintype "bidirectional"))
    )
    (net (code "23") (name "N$17") (class "Default")
      (node (ref "SENSOR2") (pin "2") (pinfunction "CSB_2") (pintype "input"))
      (node (ref "SENSOR2") (pin "6") (pinfunction "VDDIO_6") (pintype "power_in"))
      (node (ref "SENSOR2") (pin "8") (pinfunction "VDD_8") (pintype "power_in"))
    )
    (net (code "24") (name "Net-(CHG_LED-PadC)") (class "Default")
      (node (ref "CHG_LED") (pin "C") (pinfunction "C_C") (pintype "passive"))
      (node (ref "R1_BAT") (pin "2") (pinfunction "2_2") (pintype "passive"))
    )
    (net (code "25") (name "Net-(D2-CATHODE)") (class "Default")
      (node (ref "C1_BAT1") (pin "1") (pinfunction "1_1") (pintype "passive"))
      (node (ref "D2") (pin "1") (pinfunction "CATHODE_1") (pintype "bidirectional"))
      (node (ref "IC4") (pin "1") (pinfunction "VIN_1") (pintype "bidirectional"))
      (node (ref "IC4") (pin "3") (pinfunction "CE_3") (pintype "bidirectional"))
      (node (ref "Q1") (pin "2") (pinfunction "S_2") (pintype "bidirectional"))
    )
    (net (code "26") (name "Net-(D3-A)") (class "Default")
      (node (ref "C4") (pin "1") (pinfunction "1_1") (pintype "passive"))
      (node (ref "D3") (pin "2") (pinfunction "A_2") (pintype "bidirectional"))
      (node (ref "D4") (pin "1") (pinfunction "K_1") (pintype "bidirectional"))
    )
    (net (code "27") (name "Net-(D7-CATHODE)") (class "Default")
      (node (ref "D7") (pin "1") (pinfunction "CATHODE_1") (pintype "bidirectional"))
      (node (ref "R_CAPACITOR") (pin "2") (pinfunction "2_2") (pintype "passive"))
    )
    (net (code "28") (name "Net-(EPD_C1-Pad2)") (class "Default")
      (node (ref "EPD_C1") (pin "2") (pinfunction "2_2") (pintype "passive"))
      (node (ref "J1") (pin "4") (pinfunction "4_4") (pintype "bidirectional"))
    )
    (net (code "29") (name "Net-(EPD_C2-Pad2)") (class "Default")
      (node (ref "EPD_C2") (pin "2") (pinfunction "2_2") (pintype "passive"))
      (node (ref "J1") (pin "5") (pinfunction "5_5") (pintype "bidirectional"))
    )
    (net (code "30") (name "Net-(EPD_C6-Pad2)") (class "Default")
      (node (ref "EPD_C6") (pin "2") (pinfunction "2_2") (pintype "passive"))
      (node (ref "J1") (pin "18") (pinfunction "18_18") (pintype "bidirectional"))
    )
    (net (code "31") (name "Net-(EPD_C7-Pad2)") (class "Default")
      (node (ref "EPD_C7") (pin "2") (pinfunction "2_2") (pintype "passive"))
      (node (ref "J1") (pin "19") (pinfunction "19_19") (pintype "bidirectional"))
    )
    (net (code "32") (name "Net-(EPD_C8-Pad2)") (class "Default")
      (node (ref "EPD_C8") (pin "2") (pinfunction "2_2") (pintype "passive"))
      (node (ref "J1") (pin "20") (pinfunction "20_20") (pintype "bidirectional"))
    )
    (net (code "33") (name "Net-(EPD_C10-Pad2)") (class "Default")
      (node (ref "EPD_C10") (pin "2") (pinfunction "2_2") (pintype "passive"))
      (node (ref "J1") (pin "22") (pinfunction "22_22") (pintype "bidirectional"))
    )
    (net (code "34") (name "Net-(EPD_C12-Pad2)") (class "Default")
      (node (ref "EPD_C12") (pin "2") (pinfunction "2_2") (pintype "passive"))
      (node (ref "J1") (pin "24") (pinfunction "24_24") (pintype "bidirectional"))
    )
    (net (code "35") (name "Net-(IC1-CT)") (class "Default")
      (node (ref "C_DELAY") (pin "1") (pinfunction "1_1") (pintype "passive"))
      (node (ref "IC1") (pin "5") (pinfunction "CT_5") (pintype "bidirectional"))
    )
    (net (code "36") (name "Net-(J2-PadA5)") (class "Default")
      (node (ref "J2") (pin "A5") (pinfunction "A5_A5") (pintype "bidirectional"))
      (node (ref "R2-USB1") (pin "2") (pinfunction "2_2") (pintype "passive"))
    )
    (net (code "37") (name "Net-(J2-PadB5)") (class "Default")
      (node (ref "J2") (pin "B5") (pinfunction "B5_B5") (pintype "bidirectional"))
      (node (ref "R2-USB") (pin "1") (pinfunction "1_1") (pintype "passive"))
    )
    (net (code "38") (name "Net-(MCP73831-PROG)") (class "Default")
      (node (ref "MCP73831") (pin "5") (pinfunction "PROG_5") (pintype "input"))
      (node (ref "R2_BAT") (pin "2") (pinfunction "2_2") (pintype "passive"))
    )
    (net (code "39") (name "Net-(MCP73831-STAT)") (class "Default")
      (node (ref "MCP73831") (pin "1") (pinfunction "STAT_1") (pintype "output"))
      (node (ref "R1_BAT") (pin "1") (pinfunction "1_1") (pintype "passive"))
    )
    (net (code "40") (name "PREVGH") (class "Default")
      (node (ref "D5") (pin "1") (pinfunction "K_1") (pintype "bidirectional"))
      (node (ref "EPD_C9") (pin "2") (pinfunction "2_2") (pintype "passive"))
      (node (ref "J1") (pin "21") (pinfunction "21_21") (pintype "bidirectional"))
    )
    (net (code "41") (name "PREVGL") (class "Default")
      (node (ref "D4") (pin "2") (pinfunction "A_2") (pintype "bidirectional"))
      (node (ref "EPD_C11") (pin "2") (pinfunction "2_2") (pintype "passive"))
      (node (ref "J1") (pin "23") (pinfunction "23_23") (pintype "bidirectional"))
    )
    (net (code "42") (name "RESE") (class "Default")
      (node (ref "J1") (pin "3") (pinfunction "3_3") (pintype "bidirectional"))
      (node (ref "Q3") (pin "2") (pinfunction "S_2") (pintype "bidirectional"))
      (node (ref "R3") (pin "1") (pinfunction "1_1") (pintype "passive"))
    )
    (net (code "43") (name "RESE'") (class "Default")
      (node (ref "R2") (pin "2") (pinfunction "2_2") (pintype "passive"))
      (node (ref "R3") (pin "2") (pinfunction "2_2") (pintype "passive"))
      (node (ref "SJ1") (pin "2") (pinfunction "2_2") (pintype "passive"))
    )
    (net (code "44") (name "RESET") (class "Default")
      (node (ref "C5") (pin "1") (pinfunction "1_1") (pintype "passive"))
      (node (ref "IC1") (pin "1") (pinfunction "VOUT_1") (pintype "bidirectional"))
      (node (ref "RESET_BUTTON") (pin "3") (pinfunction "3_3") (pintype "passive"))
      (node (ref "RESET_BUTTON") (pin "4") (pinfunction "4_4") (pintype "passive"))
      (node (ref "R_RESET") (pin "1") (pinfunction "1_1") (pintype "passive"))
      (node (ref "U2") (pin "3") (pinfunction "EN_3") (pintype "input"))
    )
    (net (code "45") (name "RTC_RST") (class "Default")
      (node (ref "U2") (pin "16") (pinfunction "IO18_16") (pintype "bidirectional"))
      (node (ref "U3") (pin "4") (pinfunction "~{RST}_4") (pintype "input"))
    )
    (net (code "46") (name "RX") (class "Default")
      (node (ref "TP2") (pin "TP") (pinfunction "TP_TP") (pintype "input"))
      (node (ref "U2") (pin "24") (pinfunction "RXD0/GPIO17_24") (pintype "bidirectional"))
    )
    (net (code "47") (name "SCK") (class "Default")
      (node (ref "D10") (pin "1") (pinfunction "1_1") (pintype "passive"))
      (node (ref "J1") (pin "13") (pinfunction "13_13") (pintype "bidirectional"))
      (node (ref "J4") (pin "P5") (pinfunction "CLK_P5") (pintype "bidirectional"))
      (node (ref "R6") (pin "1") (pinfunction "1_1") (pintype "passive"))
      (node (ref "TP8") (pin "TP") (pinfunction "TP_TP") (pintype "input"))
      (node (ref "U1") (pin "6") (pinfunction "CLK_6") (pintype "input"))
      (node (ref "U2") (pin "6") (pinfunction "IO6_6") (pintype "bidirectional"))
    )
    (net (code "48") (name "SCL") (class "Default")
      (node (ref "J3") (pin "4") (pinfunction "4_4") (pintype "passive"))
      (node (ref "R2-PINH") (pin "1") (pinfunction "1_1") (pintype "passive"))
      (node (ref "SENSOR2") (pin "4") (pinfunction "SCK_4") (pintype "input"))
      (node (ref "U2") (pin "20") (pinfunction "IO22_20") (pintype "bidirectional"))
      (node (ref "U3") (pin "16") (pinfunction "SCL_16") (pintype "input"))
      (node (ref "U4") (pin "7") (pinfunction "SCL_7") (pintype "input"))
    )
    (net (code "49") (name "SDA") (class "Default")
      (node (ref "J3") (pin "3") (pinfunction "3_3") (pintype "passive"))
      (node (ref "R1_PINH") (pin "1") (pinfunction "1_1") (pintype "passive"))
      (node (ref "SENSOR2") (pin "3") (pinfunction "SDI_3") (pintype "bidirectional"))
      (node (ref "U2") (pin "19") (pinfunction "IO21_19") (pintype "bidirectional"))
      (node (ref "U3") (pin "15") (pinfunction "SDA_15") (pintype "bidirectional"))
      (node (ref "U4") (pin "8") (pinfunction "SDA_8") (pintype "bidirectional"))
    )
    (net (code "50") (name "SRC") (class "Default")
      (node (ref "C4") (pin "2") (pinfunction "2_2") (pintype "passive"))
      (node (ref "D5") (pin "2") (pinfunction "A_2") (pintype "bidirectional"))
      (node (ref "L1") (pin "1") (pinfunction "1_1") (pintype "passive"))
      (node (ref "Q3") (pin "3") (pinfunction "D_3") (pintype "bidirectional"))
    )
    (net (code "51") (name "SS_SD") (class "Default")
      (node (ref "D6") (pin "1") (pinfunction "1_1") (pintype "passive"))
      (node (ref "J4") (pin "P2") (pinfunction "CD/DAT3_P2") (pintype "bidirectional"))
      (node (ref "R10") (pin "1") (pinfunction "1_1") (pintype "passive"))
      (node (ref "U2") (pin "4") (pinfunction "IO4_4") (pintype "bidirectional"))
    )
    (net (code "52") (name "TX") (class "Default")
      (node (ref "TP1") (pin "TP") (pinfunction "TP_TP") (pintype "input"))
      (node (ref "U2") (pin "25") (pinfunction "TXD0/GPIO16_25") (pintype "bidirectional"))
    )
    (net (code "53") (name "USB_D+") (class "Default")
      (node (ref "D1") (pin "1") (pinfunction "I/O1_1_1") (pintype "bidirectional"))
      (node (ref "U2") (pin "14") (pinfunction "IO13_14") (pintype "bidirectional"))
    )
    (net (code "54") (name "USB_D-") (class "Default")
      (node (ref "D1") (pin "3") (pinfunction "I/O2_1_3") (pintype "bidirectional"))
      (node (ref "U2") (pin "13") (pinfunction "IO12_13") (pintype "bidirectional"))
    )
    (net (code "55") (name "VBAT") (class "Default")
      (node (ref "C2_BAT") (pin "1") (pinfunction "1_1") (pintype "passive"))
      (node (ref "MCP73831") (pin "3") (pinfunction "VBAT_3") (pintype "power_in"))
      (node (ref "Q1") (pin "3") (pinfunction "D_3") (pintype "bidirectional"))
      (node (ref "TP3") (pin "TP") (pinfunction "TP_TP") (pintype "input"))
      (node (ref "U4") (pin "2") (pinfunction "CELL_2") (pintype "power_in"))
      (node (ref "U4") (pin "3") (pinfunction "VDD_3") (pintype "power_in"))
    )
    (net (code "56") (name "VBUS") (class "Default")
      (node (ref "C1_BAT") (pin "1") (pinfunction "1_1") (pintype "passive"))
      (node (ref "C4_USB") (pin "1") (pinfunction "1_1") (pintype "passive"))
      (node (ref "C5_USB") (pin "1") (pinfunction "1_1") (pintype "passive"))
      (node (ref "CHG_LED") (pin "A") (pinfunction "A_A") (pintype "passive"))
      (node (ref "D1") (pin "5") (pinfunction "VBUS_5") (pintype "bidirectional"))
      (node (ref "D2") (pin "2") (pinfunction "ANODE_2") (pintype "bidirectional"))
      (node (ref "MCP73831") (pin "4") (pinfunction "VIN_4") (pintype "power_in"))
      (node (ref "PFMF.050.1") (pin "2") (pinfunction "2_2") (pintype "passive"))
      (node (ref "Q1") (pin "1") (pinfunction "G_1") (pintype "bidirectional"))
      (node (ref "R1_PWRUSB") (pin "2") (pinfunction "2_2") (pintype "passive"))
      (node (ref "TP14") (pin "TP") (pinfunction "TP_TP") (pintype "input"))
    )
    (net (code "57") (name "VRTC") (class "Default")
      (node (ref "C10_SUPERCAP") (pin "2") (pinfunction "2_2") (pintype "passive"))
      (node (ref "C8") (pin "1") (pinfunction "1_1") (pintype "passive"))
      (node (ref "R_CAPACITOR") (pin "1") (pinfunction "1_1") (pintype "passive"))
      (node (ref "U3") (pin "14") (pinfunction "VBAT_14") (pintype "power_in"))
    )
    (net (code "58") (name "VUSB") (class "Default")
      (node (ref "J2") (pin "A4") (pinfunction "A4_A4") (pintype "bidirectional"))
      (node (ref "J2") (pin "A9") (pinfunction "A9_A9") (pintype "bidirectional"))
      (node (ref "J2") (pin "B4") (pinfunction "B4_B4") (pintype "bidirectional"))
      (node (ref "J2") (pin "B9") (pinfunction "B9_B9") (pintype "bidirectional"))
      (node (ref "PFMF.050.1") (pin "1") (pinfunction "1_1") (pintype "passive"))
    )
    (net (code "59") (name "unconnected-(IC1-NC-Pad4)") (class "Default")
      (node (ref "IC1") (pin "4") (pinfunction "NC_4") (pintype "no_connect"))
    )
    (net (code "60") (name "unconnected-(IC1-VDD-Pad2)") (class "Default")
      (node (ref "IC1") (pin "2") (pinfunction "VDD_2") (pintype "bidirectional"))
    )
    (net (code "61") (name "unconnected-(IC4-NC-Pad4)") (class "Default")
      (node (ref "IC4") (pin "4") (pinfunction "NC_4") (pintype "no_connect"))
    )
    (net (code "62") (name "unconnected-(J1-Pad1)") (class "Default")
      (node (ref "J1") (pin "1") (pinfunction "1_1") (pintype "bidirectional"))
    )
    (net (code "63") (name "unconnected-(J1-Pad6)") (class "Default")
      (node (ref "J1") (pin "6") (pinfunction "6_6") (pintype "bidirectional"))
    )
    (net (code "64") (name "unconnected-(J1-Pad7)") (class "Default")
      (node (ref "J1") (pin "7") (pinfunction "7_7") (pintype "bidirectional"))
    )
    (net (code "65") (name "unconnected-(J2-PadA8)") (class "Default")
      (node (ref "J2") (pin "A8") (pinfunction "A8_A8") (pintype "bidirectional"))
    )
    (net (code "66") (name "unconnected-(J2-PadB8)") (class "Default")
      (node (ref "J2") (pin "B8") (pinfunction "B8_B8") (pintype "bidirectional"))
    )
    (net (code "67") (name "unconnected-(J4-DAT1-PadP8)") (class "Default")
      (node (ref "J4") (pin "P8") (pinfunction "DAT1_P8") (pintype "bidirectional"))
    )
    (net (code "68") (name "unconnected-(J4-DAT2-PadP1)") (class "Default")
      (node (ref "J4") (pin "P1") (pinfunction "DAT2_P1") (pintype "bidirectional"))
    )
    (net (code "69") (name "unconnected-(J4-DETECTION_1-PadS1)") (class "Default")
      (node (ref "J4") (pin "S1") (pinfunction "DETECTION_1_S1") (pintype "bidirectional"))
    )
    (net (code "70") (name "unconnected-(J4-DETECTION_2-PadS2)") (class "Default")
      (node (ref "J4") (pin "S2") (pinfunction "DETECTION_2_S2") (pintype "bidirectional"))
    )
    (net (code "71") (name "unconnected-(U2-NC-Pad22)") (class "Default")
      (node (ref "U2") (pin "22") (pinfunction "NC_22") (pintype "no_connect"))
    )
    (net (code "72") (name "unconnected-(U4-~{ALERT}-Pad5)") (class "Default")
      (node (ref "U4") (pin "5") (pinfunction "~{ALERT}_5") (pintype "output"))
    )
  )
)
